# base-v2.net
KiCad netlist of a schematic drawn in EAGLE
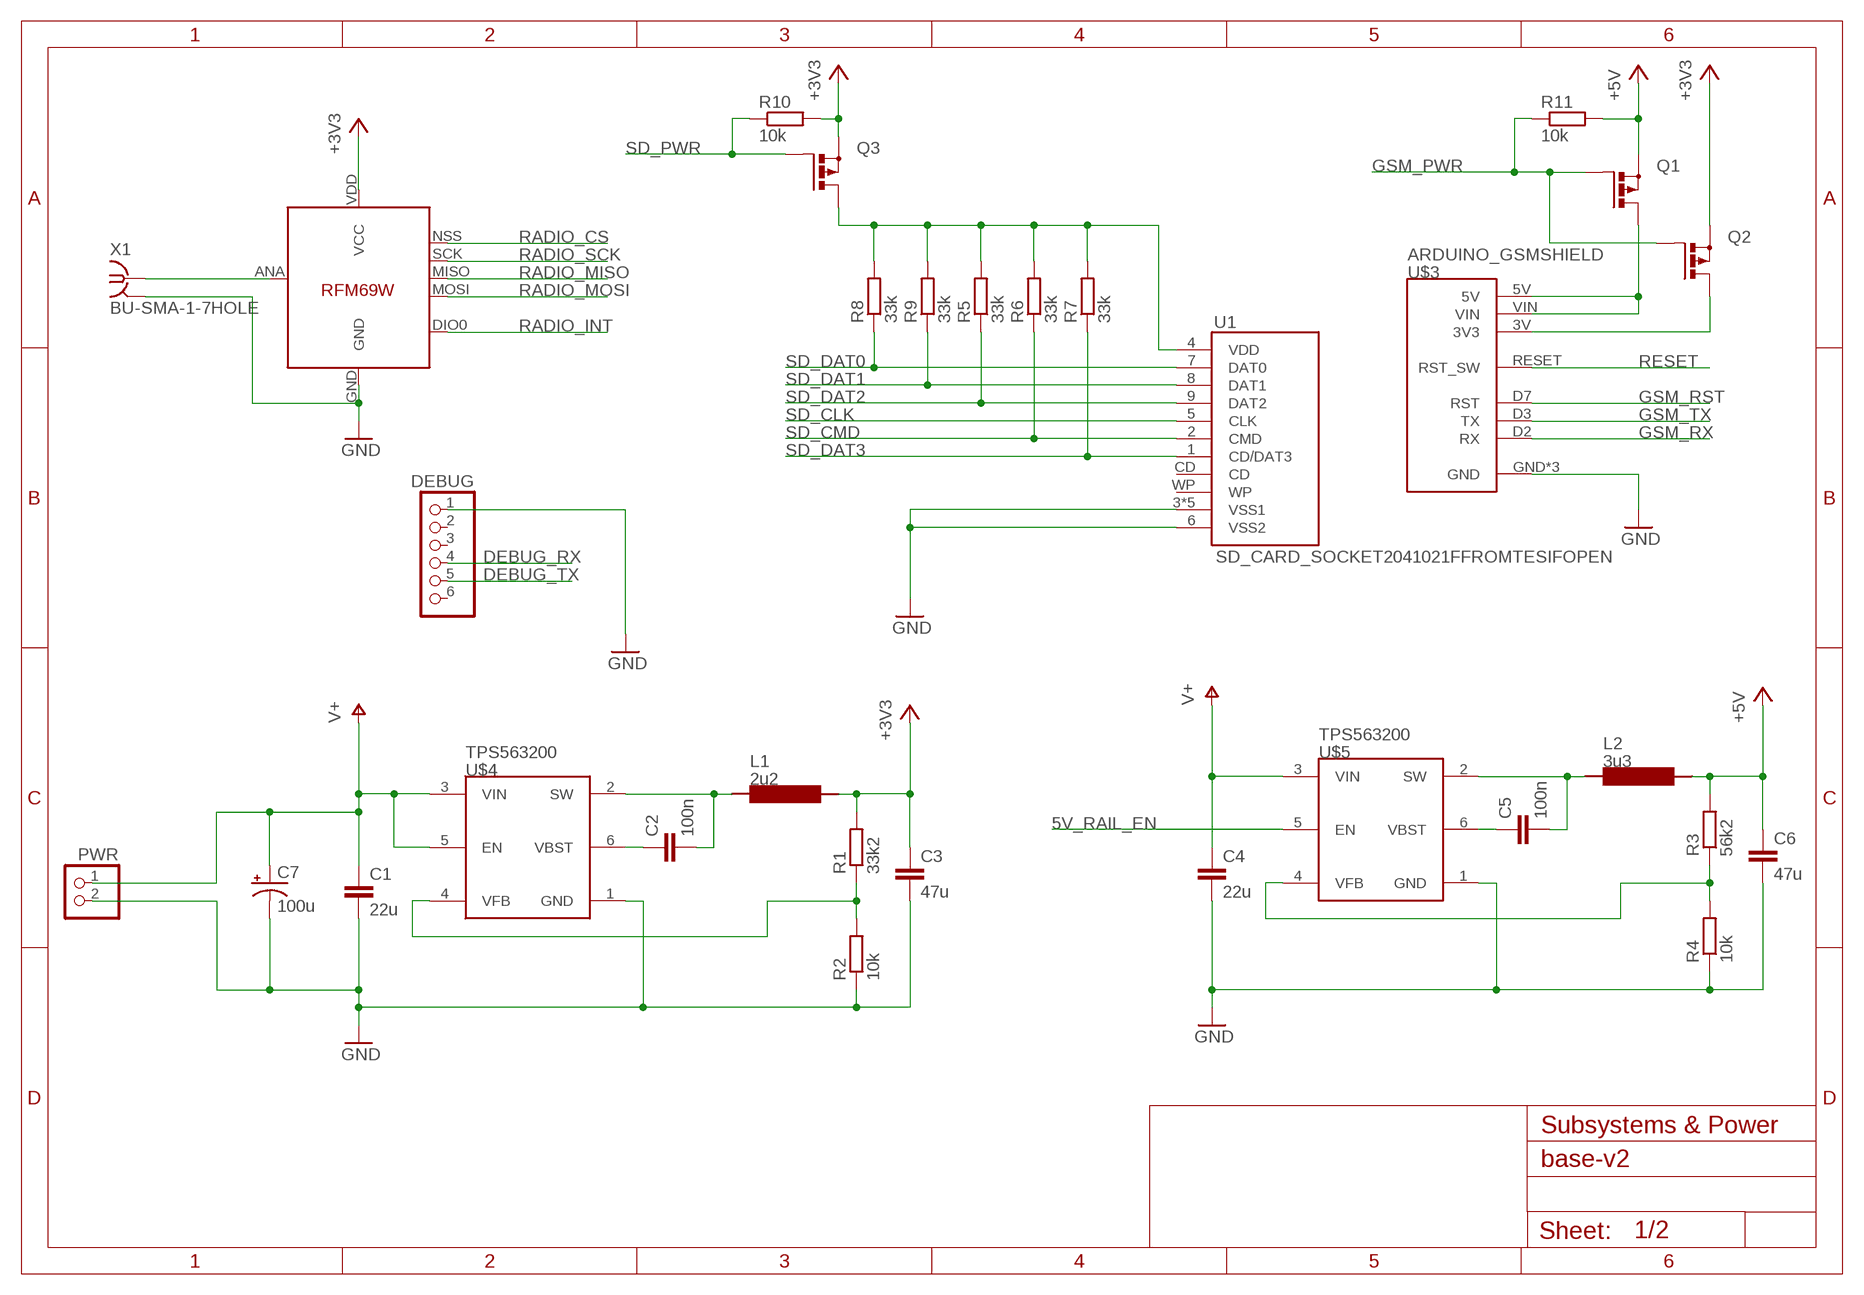
[diagram p0: schematic, sheet 1]
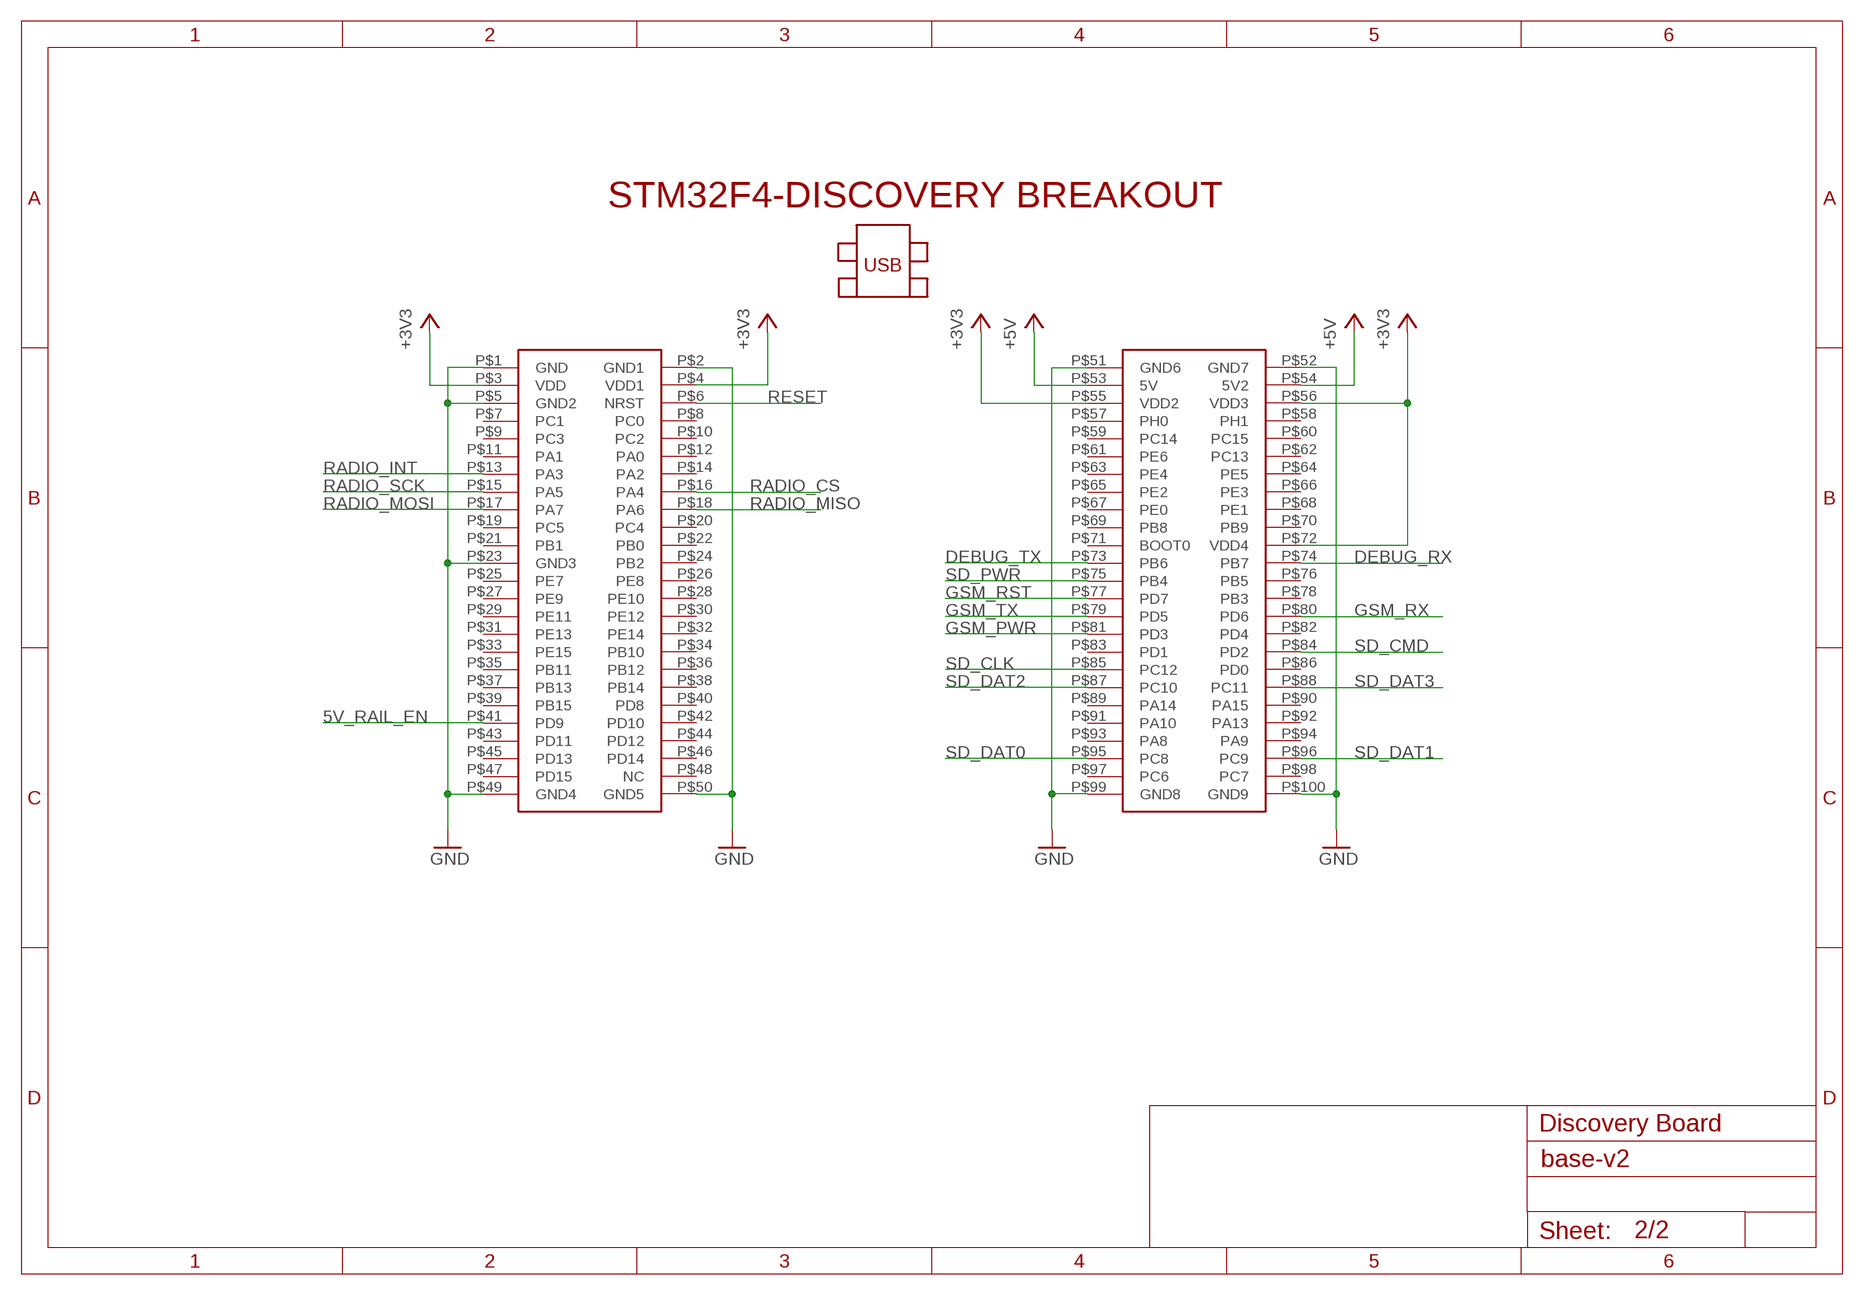
[diagram p1: schematic, sheet 2]

(export (version "E")
  (design (tool "Eeschema 10.0.6"))
  (components
    (comp (ref "C1")
      (value "22u")
      (footprint "eagle-import:1206")
      (libsource (lib "eagle-import") (part "CAP1206"))
    )
    (comp (ref "C2")
      (value "100n")
      (footprint "eagle-import:CAP-PTH-SMALL")
      (libsource (lib "eagle-import") (part "CAPPTH"))
    )
    (comp (ref "C3")
      (value "47u")
      (footprint "eagle-import:1206")
      (libsource (lib "eagle-import") (part "CAP1206"))
    )
    (comp (ref "C4")
      (value "22u")
      (footprint "eagle-import:1206")
      (libsource (lib "eagle-import") (part "CAP1206"))
    )
    (comp (ref "C5")
      (value "100n")
      (footprint "eagle-import:CAP-PTH-SMALL")
      (libsource (lib "eagle-import") (part "CAPPTH"))
    )
    (comp (ref "C6")
      (value "47u")
      (footprint "eagle-import:1206")
      (libsource (lib "eagle-import") (part "CAP1206"))
    )
    (comp (ref "C7")
      (value "100u")
      (footprint "eagle-import:CPOL-RADIAL-10UF-25V")
      (libsource (lib "eagle-import") (part "CAP_POLPTH2"))
    )
    (comp (ref "DEBUG")
      (value "PINHD-1X6")
      (footprint "eagle-import:1X06")
      (libsource (lib "eagle-import") (part "PINHD-1X6"))
    )
    (comp (ref "L1")
      (value "2u2")
      (footprint "eagle-import:SRR7032")
      (libsource (lib "eagle-import") (part "SRR7032"))
    )
    (comp (ref "L2")
      (value "3u3")
      (footprint "eagle-import:SRR7032")
      (libsource (lib "eagle-import") (part "SRR7032"))
    )
    (comp (ref "PWR")
      (value "PINHD-1X2")
      (footprint "eagle-import:1X02")
      (libsource (lib "eagle-import") (part "PINHD-1X2"))
    )
    (comp (ref "Q1")
      (value "PMOSFET_PTO220BH")
      (footprint "eagle-import:TO220BH")
      (libsource (lib "eagle-import") (part "PMOSFET_PTO220BH"))
    )
    (comp (ref "Q2")
      (value "PMOSFET_PTO220BH")
      (footprint "eagle-import:TO220BH")
      (libsource (lib "eagle-import") (part "PMOSFET_PTO220BH"))
    )
    (comp (ref "Q3")
      (value "PMOSFET_PTO220BH")
      (footprint "eagle-import:TO220BH")
      (libsource (lib "eagle-import") (part "PMOSFET_PTO220BH"))
    )
    (comp (ref "R1")
      (value "33k2")
      (footprint "eagle-import:0204_7")
      (libsource (lib "eagle-import") (part "R-EU_0204/7"))
    )
    (comp (ref "R2")
      (value "10k")
      (footprint "eagle-import:0204_7")
      (libsource (lib "eagle-import") (part "R-EU_0204/7"))
    )
    (comp (ref "R3")
      (value "56k2")
      (footprint "eagle-import:0204_7")
      (libsource (lib "eagle-import") (part "R-EU_0204/7"))
    )
    (comp (ref "R4")
      (value "10k")
      (footprint "eagle-import:0204_7")
      (libsource (lib "eagle-import") (part "R-EU_0204/7"))
    )
    (comp (ref "R5")
      (value "33k")
      (footprint "eagle-import:0204_7")
      (libsource (lib "eagle-import") (part "R-EU_0204/7"))
    )
    (comp (ref "R6")
      (value "33k")
      (footprint "eagle-import:0204_7")
      (libsource (lib "eagle-import") (part "R-EU_0204/7"))
    )
    (comp (ref "R7")
      (value "33k")
      (footprint "eagle-import:0204_7")
      (libsource (lib "eagle-import") (part "R-EU_0204/7"))
    )
    (comp (ref "R8")
      (value "33k")
      (footprint "eagle-import:0204_7")
      (libsource (lib "eagle-import") (part "R-EU_0204/7"))
    )
    (comp (ref "R9")
      (value "33k")
      (footprint "eagle-import:0204_7")
      (libsource (lib "eagle-import") (part "R-EU_0204/7"))
    )
    (comp (ref "R10")
      (value "10k")
      (footprint "eagle-import:0204_7")
      (libsource (lib "eagle-import") (part "R-EU_0204/7"))
    )
    (comp (ref "R11")
      (value "10k")
      (footprint "eagle-import:0204_7")
      (libsource (lib "eagle-import") (part "R-EU_0204/7"))
    )
    (comp (ref "U$2")
      (value "RFM69")
      (footprint "eagle-import:RFM69W-MINPADS")
      (libsource (lib "eagle-import") (part "RFM69"))
    )
    (comp (ref "U$3")
      (value "ARDUINO_GSMSHIELD")
      (footprint "eagle-import:ARDUINO-NOHOLE")
      (libsource (lib "eagle-import") (part "ARDUINO_GSMSHIELD"))
    )
    (comp (ref "U$4")
      (value "TPS563200")
      (footprint "eagle-import:DDC0006A")
      (libsource (lib "eagle-import") (part "TPS563200"))
    )
    (comp (ref "U$5")
      (value "TPS563200")
      (footprint "eagle-import:DDC0006A")
      (libsource (lib "eagle-import") (part "TPS563200"))
    )
    (comp (ref "U1")
      (value "SD_CARD_SOCKET2041021FFROMTESIFOPEN")
      (footprint "eagle-import:SDCARD_2041021-3")
      (libsource (lib "eagle-import") (part "SD_CARD_SOCKET2041021FFROMTESIFOPEN"))
    )
    (comp (ref "X1")
      (value "BU-SMA-1-7HOLE")
      (footprint "eagle-import:SMA_1-7HOLES")
      (libsource (lib "eagle-import") (part "BU-SMA-1-7HOLE"))
    )
    (comp (ref "U$1")
      (value "STM32F4-DISCOVERY")
      (footprint "eagle-import:STM32F4-DISCOVERY")
      (libsource (lib "eagle-import") (part "STM32F4-DISCOVERY"))
    )
  )
  (nets
    (net (code "1") (name "+3V3") (class "Default")
      (node (ref "C3") (pin "1") (pinfunction "1_1") (pintype "passive"))
      (node (ref "L1") (pin "2") (pinfunction "2_2") (pintype "passive"))
      (node (ref "Q2") (pin "S") (pinfunction "S_S") (pintype "passive"))
      (node (ref "Q3") (pin "S") (pinfunction "S_S") (pintype "passive"))
      (node (ref "R1") (pin "2") (pinfunction "2_2") (pintype "passive"))
      (node (ref "R10") (pin "2") (pinfunction "2_2") (pintype "passive"))
      (node (ref "U$1") (pin "P$3") (pinfunction "VDD_P$3") (pintype "bidirectional"))
      (node (ref "U$1") (pin "P$4") (pinfunction "VDD1_P$4") (pintype "bidirectional"))
      (node (ref "U$1") (pin "P$55") (pinfunction "VDD2_P$55") (pintype "bidirectional"))
      (node (ref "U$1") (pin "P$56") (pinfunction "VDD3_P$56") (pintype "bidirectional"))
      (node (ref "U$1") (pin "P$72") (pinfunction "VDD4_P$72") (pintype "bidirectional"))
      (node (ref "U$2") (pin "VDD") (pinfunction "VCC_VDD") (pintype "power_in"))
    )
    (net (code "2") (name "+5V") (class "Default")
      (node (ref "C6") (pin "1") (pinfunction "1_1") (pintype "passive"))
      (node (ref "L2") (pin "2") (pinfunction "2_2") (pintype "passive"))
      (node (ref "Q1") (pin "S") (pinfunction "S_S") (pintype "passive"))
      (node (ref "R11") (pin "2") (pinfunction "2_2") (pintype "passive"))
      (node (ref "R3") (pin "2") (pinfunction "2_2") (pintype "passive"))
      (node (ref "U$1") (pin "P$53") (pinfunction "5V_P$53") (pintype "bidirectional"))
      (node (ref "U$1") (pin "P$54") (pinfunction "5V2_P$54") (pintype "bidirectional"))
    )
    (net (code "3") (name "5V_RAIL_EN") (class "Default")
      (node (ref "U$1") (pin "P$41") (pinfunction "PD9_P$41") (pintype "bidirectional"))
      (node (ref "U$5") (pin "5") (pinfunction "EN_5") (pintype "bidirectional"))
    )
    (net (code "4") (name "DEBUG_RX") (class "Default")
      (node (ref "DEBUG") (pin "4") (pinfunction "4_4") (pintype "passive"))
      (node (ref "U$1") (pin "P$74") (pinfunction "PB7_P$74") (pintype "bidirectional"))
    )
    (net (code "5") (name "DEBUG_TX") (class "Default")
      (node (ref "DEBUG") (pin "5") (pinfunction "5_5") (pintype "passive"))
      (node (ref "U$1") (pin "P$73") (pinfunction "PB6_P$73") (pintype "bidirectional"))
    )
    (net (code "6") (name "GND") (class "Default")
      (node (ref "C1") (pin "2") (pinfunction "2_2") (pintype "passive"))
      (node (ref "C3") (pin "2") (pinfunction "2_2") (pintype "passive"))
      (node (ref "C4") (pin "2") (pinfunction "2_2") (pintype "passive"))
      (node (ref "C6") (pin "2") (pinfunction "2_2") (pintype "passive"))
      (node (ref "C7") (pin "2") (pinfunction "-_2") (pintype "passive"))
      (node (ref "DEBUG") (pin "1") (pinfunction "1_1") (pintype "passive"))
      (node (ref "PWR") (pin "2") (pinfunction "2_2") (pintype "passive"))
      (node (ref "R2") (pin "1") (pinfunction "1_1") (pintype "passive"))
      (node (ref "R4") (pin "1") (pinfunction "1_1") (pintype "passive"))
      (node (ref "U$1") (pin "P$1") (pinfunction "GND_P$1") (pintype "bidirectional"))
      (node (ref "U$1") (pin "P$100") (pinfunction "GND9_P$100") (pintype "bidirectional"))
      (node (ref "U$1") (pin "P$2") (pinfunction "GND1_P$2") (pintype "bidirectional"))
      (node (ref "U$1") (pin "P$23") (pinfunction "GND3_P$23") (pintype "bidirectional"))
      (node (ref "U$1") (pin "P$49") (pinfunction "GND4_P$49") (pintype "bidirectional"))
      (node (ref "U$1") (pin "P$5") (pinfunction "GND2_P$5") (pintype "bidirectional"))
      (node (ref "U$1") (pin "P$50") (pinfunction "GND5_P$50") (pintype "bidirectional"))
      (node (ref "U$1") (pin "P$51") (pinfunction "GND6_P$51") (pintype "bidirectional"))
      (node (ref "U$1") (pin "P$52") (pinfunction "GND7_P$52") (pintype "bidirectional"))
      (node (ref "U$1") (pin "P$99") (pinfunction "GND8_P$99") (pintype "bidirectional"))
      (node (ref "U$2") (pin "GND") (pinfunction "GND_GND") (pintype "power_in"))
      (node (ref "U$3") (pin "GND") (pinfunction "GND_GND") (pintype "bidirectional"))
      (node (ref "U$3") (pin "GND1") (pinfunction "GND_GND1") (pintype "bidirectional"))
      (node (ref "U$3") (pin "GND2") (pinfunction "GND_GND2") (pintype "bidirectional"))
      (node (ref "U$4") (pin "1") (pinfunction "GND_1") (pintype "bidirectional"))
      (node (ref "U$5") (pin "1") (pinfunction "GND_1") (pintype "bidirectional"))
      (node (ref "U1") (pin "3") (pinfunction "VSS1_3") (pintype "power_in"))
      (node (ref "U1") (pin "6") (pinfunction "VSS2_6") (pintype "power_in"))
      (node (ref "U1") (pin "SH1") (pinfunction "VSS1_SH1") (pintype "power_in"))
      (node (ref "U1") (pin "SH2") (pinfunction "VSS1_SH2") (pintype "power_in"))
      (node (ref "U1") (pin "SH3") (pinfunction "VSS1_SH3") (pintype "power_in"))
      (node (ref "U1") (pin "SH4") (pinfunction "VSS1_SH4") (pintype "power_in"))
      (node (ref "X1") (pin "2") (pinfunction "2_2") (pintype "passive"))
      (node (ref "X1") (pin "3") (pinfunction "2_3") (pintype "passive"))
      (node (ref "X1") (pin "4") (pinfunction "2_4") (pintype "passive"))
      (node (ref "X1") (pin "5") (pinfunction "2_5") (pintype "passive"))
    )
    (net (code "7") (name "GSM_PWR") (class "Default")
      (node (ref "Q1") (pin "G") (pinfunction "G_G") (pintype "passive"))
      (node (ref "Q2") (pin "G") (pinfunction "G_G") (pintype "passive"))
      (node (ref "R11") (pin "1") (pinfunction "1_1") (pintype "passive"))
      (node (ref "U$1") (pin "P$81") (pinfunction "PD3_P$81") (pintype "bidirectional"))
    )
    (net (code "8") (name "GSM_RST") (class "Default")
      (node (ref "U$1") (pin "P$77") (pinfunction "PD7_P$77") (pintype "bidirectional"))
      (node (ref "U$3") (pin "D7") (pinfunction "RST_D7") (pintype "bidirectional"))
    )
    (net (code "9") (name "GSM_RX") (class "Default")
      (node (ref "U$1") (pin "P$80") (pinfunction "PD6_P$80") (pintype "bidirectional"))
      (node (ref "U$3") (pin "D2") (pinfunction "RX_D2") (pintype "bidirectional"))
    )
    (net (code "10") (name "GSM_TX") (class "Default")
      (node (ref "U$1") (pin "P$79") (pinfunction "PD5_P$79") (pintype "bidirectional"))
      (node (ref "U$3") (pin "D3") (pinfunction "TX_D3") (pintype "bidirectional"))
    )
    (net (code "11") (name "Net-(Q1-PadD)") (class "Default")
      (node (ref "Q1") (pin "D") (pinfunction "D_D") (pintype "passive"))
      (node (ref "U$3") (pin "5V") (pinfunction "5V_5V") (pintype "bidirectional"))
      (node (ref "U$3") (pin "VIN") (pinfunction "VIN_VIN") (pintype "bidirectional"))
    )
    (net (code "12") (name "Net-(U$2-ANT)") (class "Default")
      (node (ref "U$2") (pin "ANA") (pinfunction "ANT_ANA") (pintype "passive"))
      (node (ref "X1") (pin "1") (pinfunction "1_1") (pintype "passive"))
    )
    (net (code "13") (name "Net-(U$3-3V3)") (class "Default")
      (node (ref "Q2") (pin "D") (pinfunction "D_D") (pintype "passive"))
      (node (ref "U$3") (pin "3V") (pinfunction "3V3_3V") (pintype "bidirectional"))
    )
    (net (code "14") (name "Net-(U$4-SW)") (class "Default")
      (node (ref "C2") (pin "2") (pinfunction "2_2") (pintype "passive"))
      (node (ref "L1") (pin "1") (pinfunction "1_1") (pintype "passive"))
      (node (ref "U$4") (pin "2") (pinfunction "SW_2") (pintype "bidirectional"))
    )
    (net (code "15") (name "Net-(U$4-VBST)") (class "Default")
      (node (ref "C2") (pin "1") (pinfunction "1_1") (pintype "passive"))
      (node (ref "U$4") (pin "6") (pinfunction "VBST_6") (pintype "bidirectional"))
    )
    (net (code "16") (name "Net-(U$4-VFB)") (class "Default")
      (node (ref "R1") (pin "1") (pinfunction "1_1") (pintype "passive"))
      (node (ref "R2") (pin "2") (pinfunction "2_2") (pintype "passive"))
      (node (ref "U$4") (pin "4") (pinfunction "VFB_4") (pintype "bidirectional"))
    )
    (net (code "17") (name "Net-(U$5-SW)") (class "Default")
      (node (ref "C5") (pin "2") (pinfunction "2_2") (pintype "passive"))
      (node (ref "L2") (pin "1") (pinfunction "1_1") (pintype "passive"))
      (node (ref "U$5") (pin "2") (pinfunction "SW_2") (pintype "bidirectional"))
    )
    (net (code "18") (name "Net-(U$5-VBST)") (class "Default")
      (node (ref "C5") (pin "1") (pinfunction "1_1") (pintype "passive"))
      (node (ref "U$5") (pin "6") (pinfunction "VBST_6") (pintype "bidirectional"))
    )
    (net (code "19") (name "Net-(U$5-VFB)") (class "Default")
      (node (ref "R3") (pin "1") (pinfunction "1_1") (pintype "passive"))
      (node (ref "R4") (pin "2") (pinfunction "2_2") (pintype "passive"))
      (node (ref "U$5") (pin "4") (pinfunction "VFB_4") (pintype "bidirectional"))
    )
    (net (code "20") (name "Net-(U1-VDD)") (class "Default")
      (node (ref "Q3") (pin "D") (pinfunction "D_D") (pintype "passive"))
      (node (ref "R5") (pin "2") (pinfunction "2_2") (pintype "passive"))
      (node (ref "R6") (pin "2") (pinfunction "2_2") (pintype "passive"))
      (node (ref "R7") (pin "2") (pinfunction "2_2") (pintype "passive"))
      (node (ref "R8") (pin "2") (pinfunction "2_2") (pintype "passive"))
      (node (ref "R9") (pin "2") (pinfunction "2_2") (pintype "passive"))
      (node (ref "U1") (pin "4") (pinfunction "VDD_4") (pintype "power_in"))
    )
    (net (code "21") (name "RADIO_CS") (class "Default")
      (node (ref "U$1") (pin "P$16") (pinfunction "PA4_P$16") (pintype "bidirectional"))
      (node (ref "U$2") (pin "NSS") (pinfunction "SEL_NSS") (pintype "input"))
    )
    (net (code "22") (name "RADIO_INT") (class "Default")
      (node (ref "U$1") (pin "P$13") (pinfunction "PA3_P$13") (pintype "bidirectional"))
      (node (ref "U$2") (pin "DIO0") (pinfunction "DIO0_DIO0") (pintype "open_collector"))
    )
    (net (code "23") (name "RADIO_MISO") (class "Default")
      (node (ref "U$1") (pin "P$18") (pinfunction "PA6_P$18") (pintype "bidirectional"))
      (node (ref "U$2") (pin "MISO") (pinfunction "MISO_MISO") (pintype "input"))
    )
    (net (code "24") (name "RADIO_MOSI") (class "Default")
      (node (ref "U$1") (pin "P$17") (pinfunction "PA7_P$17") (pintype "bidirectional"))
      (node (ref "U$2") (pin "MOSI") (pinfunction "MOSI_MOSI") (pintype "output"))
    )
    (net (code "25") (name "RADIO_SCK") (class "Default")
      (node (ref "U$1") (pin "P$15") (pinfunction "PA5_P$15") (pintype "bidirectional"))
      (node (ref "U$2") (pin "SCK") (pinfunction "SCK_SCK") (pintype "input"))
    )
    (net (code "26") (name "RESET") (class "Default")
      (node (ref "U$1") (pin "P$6") (pinfunction "NRST_P$6") (pintype "bidirectional"))
      (node (ref "U$3") (pin "RESET") (pinfunction "RST_SW_RESET") (pintype "bidirectional"))
    )
    (net (code "27") (name "SD_CLK") (class "Default")
      (node (ref "U$1") (pin "P$85") (pinfunction "PC12_P$85") (pintype "bidirectional"))
      (node (ref "U1") (pin "5") (pinfunction "CLK_5") (pintype "bidirectional"))
    )
    (net (code "28") (name "SD_CMD") (class "Default")
      (node (ref "R6") (pin "1") (pinfunction "1_1") (pintype "passive"))
      (node (ref "U$1") (pin "P$84") (pinfunction "PD2_P$84") (pintype "bidirectional"))
      (node (ref "U1") (pin "2") (pinfunction "CMD_2") (pintype "bidirectional"))
    )
    (net (code "29") (name "SD_DAT0") (class "Default")
      (node (ref "R8") (pin "1") (pinfunction "1_1") (pintype "passive"))
      (node (ref "U$1") (pin "P$95") (pinfunction "PC8_P$95") (pintype "bidirectional"))
      (node (ref "U1") (pin "7") (pinfunction "DAT0_7") (pintype "bidirectional"))
    )
    (net (code "30") (name "SD_DAT1") (class "Default")
      (node (ref "R9") (pin "1") (pinfunction "1_1") (pintype "passive"))
      (node (ref "U$1") (pin "P$96") (pinfunction "PC9_P$96") (pintype "bidirectional"))
      (node (ref "U1") (pin "8") (pinfunction "DAT1_8") (pintype "bidirectional"))
    )
    (net (code "31") (name "SD_DAT2") (class "Default")
      (node (ref "R5") (pin "1") (pinfunction "1_1") (pintype "passive"))
      (node (ref "U$1") (pin "P$87") (pinfunction "PC10_P$87") (pintype "bidirectional"))
      (node (ref "U1") (pin "9") (pinfunction "DAT2_9") (pintype "bidirectional"))
    )
    (net (code "32") (name "SD_DAT3") (class "Default")
      (node (ref "R7") (pin "1") (pinfunction "1_1") (pintype "passive"))
      (node (ref "U$1") (pin "P$88") (pinfunction "PC11_P$88") (pintype "bidirectional"))
      (node (ref "U1") (pin "1") (pinfunction "CD/DAT3_1") (pintype "bidirectional"))
    )
    (net (code "33") (name "SD_PWR") (class "Default")
      (node (ref "Q3") (pin "G") (pinfunction "G_G") (pintype "passive"))
      (node (ref "R10") (pin "1") (pinfunction "1_1") (pintype "passive"))
      (node (ref "U$1") (pin "P$75") (pinfunction "PB4_P$75") (pintype "bidirectional"))
    )
    (net (code "34") (name "V+") (class "Default")
      (node (ref "C1") (pin "1") (pinfunction "1_1") (pintype "passive"))
      (node (ref "C4") (pin "1") (pinfunction "1_1") (pintype "passive"))
      (node (ref "C7") (pin "1") (pinfunction "+_1") (pintype "passive"))
      (node (ref "PWR") (pin "1") (pinfunction "1_1") (pintype "passive"))
      (node (ref "U$4") (pin "3") (pinfunction "VIN_3") (pintype "bidirectional"))
      (node (ref "U$4") (pin "5") (pinfunction "EN_5") (pintype "bidirectional"))
      (node (ref "U$5") (pin "3") (pinfunction "VIN_3") (pintype "bidirectional"))
    )
    (net (code "35") (name "unconnected-(DEBUG-Pad2)") (class "Default")
      (node (ref "DEBUG") (pin "2") (pinfunction "2_2") (pintype "passive"))
    )
    (net (code "36") (name "unconnected-(DEBUG-Pad3)") (class "Default")
      (node (ref "DEBUG") (pin "3") (pinfunction "3_3") (pintype "passive"))
    )
    (net (code "37") (name "unconnected-(DEBUG-Pad6)") (class "Default")
      (node (ref "DEBUG") (pin "6") (pinfunction "6_6") (pintype "passive"))
    )
    (net (code "38") (name "unconnected-(U$1-BOOT0-PadP$71)") (class "Default")
      (node (ref "U$1") (pin "P$71") (pinfunction "BOOT0_P$71") (pintype "bidirectional"))
    )
    (net (code "39") (name "unconnected-(U$1-NC-PadP$48)") (class "Default")
      (node (ref "U$1") (pin "P$48") (pinfunction "NC_P$48") (pintype "bidirectional"))
    )
    (net (code "40") (name "unconnected-(U$1-PA0-PadP$12)") (class "Default")
      (node (ref "U$1") (pin "P$12") (pinfunction "PA0_P$12") (pintype "bidirectional"))
    )
    (net (code "41") (name "unconnected-(U$1-PA1-PadP$11)") (class "Default")
      (node (ref "U$1") (pin "P$11") (pinfunction "PA1_P$11") (pintype "bidirectional"))
    )
    (net (code "42") (name "unconnected-(U$1-PA2-PadP$14)") (class "Default")
      (node (ref "U$1") (pin "P$14") (pinfunction "PA2_P$14") (pintype "bidirectional"))
    )
    (net (code "43") (name "unconnected-(U$1-PA8-PadP$93)") (class "Default")
      (node (ref "U$1") (pin "P$93") (pinfunction "PA8_P$93") (pintype "bidirectional"))
    )
    (net (code "44") (name "unconnected-(U$1-PA9-PadP$94)") (class "Default")
      (node (ref "U$1") (pin "P$94") (pinfunction "PA9_P$94") (pintype "bidirectional"))
    )
    (net (code "45") (name "unconnected-(U$1-PA10-PadP$91)") (class "Default")
      (node (ref "U$1") (pin "P$91") (pinfunction "PA10_P$91") (pintype "bidirectional"))
    )
    (net (code "46") (name "unconnected-(U$1-PA13-PadP$92)") (class "Default")
      (node (ref "U$1") (pin "P$92") (pinfunction "PA13_P$92") (pintype "bidirectional"))
    )
    (net (code "47") (name "unconnected-(U$1-PA14-PadP$89)") (class "Default")
      (node (ref "U$1") (pin "P$89") (pinfunction "PA14_P$89") (pintype "bidirectional"))
    )
    (net (code "48") (name "unconnected-(U$1-PA15-PadP$90)") (class "Default")
      (node (ref "U$1") (pin "P$90") (pinfunction "PA15_P$90") (pintype "bidirectional"))
    )
    (net (code "49") (name "unconnected-(U$1-PB0-PadP$22)") (class "Default")
      (node (ref "U$1") (pin "P$22") (pinfunction "PB0_P$22") (pintype "bidirectional"))
    )
    (net (code "50") (name "unconnected-(U$1-PB1-PadP$21)") (class "Default")
      (node (ref "U$1") (pin "P$21") (pinfunction "PB1_P$21") (pintype "bidirectional"))
    )
    (net (code "51") (name "unconnected-(U$1-PB2-PadP$24)") (class "Default")
      (node (ref "U$1") (pin "P$24") (pinfunction "PB2_P$24") (pintype "bidirectional"))
    )
    (net (code "52") (name "unconnected-(U$1-PB3-PadP$78)") (class "Default")
      (node (ref "U$1") (pin "P$78") (pinfunction "PB3_P$78") (pintype "bidirectional"))
    )
    (net (code "53") (name "unconnected-(U$1-PB5-PadP$76)") (class "Default")
      (node (ref "U$1") (pin "P$76") (pinfunction "PB5_P$76") (pintype "bidirectional"))
    )
    (net (code "54") (name "unconnected-(U$1-PB8-PadP$69)") (class "Default")
      (node (ref "U$1") (pin "P$69") (pinfunction "PB8_P$69") (pintype "bidirectional"))
    )
    (net (code "55") (name "unconnected-(U$1-PB9-PadP$70)") (class "Default")
      (node (ref "U$1") (pin "P$70") (pinfunction "PB9_P$70") (pintype "bidirectional"))
    )
    (net (code "56") (name "unconnected-(U$1-PB10-PadP$34)") (class "Default")
      (node (ref "U$1") (pin "P$34") (pinfunction "PB10_P$34") (pintype "bidirectional"))
    )
    (net (code "57") (name "unconnected-(U$1-PB11-PadP$35)") (class "Default")
      (node (ref "U$1") (pin "P$35") (pinfunction "PB11_P$35") (pintype "bidirectional"))
    )
    (net (code "58") (name "unconnected-(U$1-PB12-PadP$36)") (class "Default")
      (node (ref "U$1") (pin "P$36") (pinfunction "PB12_P$36") (pintype "bidirectional"))
    )
    (net (code "59") (name "unconnected-(U$1-PB13-PadP$37)") (class "Default")
      (node (ref "U$1") (pin "P$37") (pinfunction "PB13_P$37") (pintype "bidirectional"))
    )
    (net (code "60") (name "unconnected-(U$1-PB14-PadP$38)") (class "Default")
      (node (ref "U$1") (pin "P$38") (pinfunction "PB14_P$38") (pintype "bidirectional"))
    )
    (net (code "61") (name "unconnected-(U$1-PB15-PadP$39)") (class "Default")
      (node (ref "U$1") (pin "P$39") (pinfunction "PB15_P$39") (pintype "bidirectional"))
    )
    (net (code "62") (name "unconnected-(U$1-PC0-PadP$8)") (class "Default")
      (node (ref "U$1") (pin "P$8") (pinfunction "PC0_P$8") (pintype "bidirectional"))
    )
    (net (code "63") (name "unconnected-(U$1-PC1-PadP$7)") (class "Default")
      (node (ref "U$1") (pin "P$7") (pinfunction "PC1_P$7") (pintype "bidirectional"))
    )
    (net (code "64") (name "unconnected-(U$1-PC2-PadP$10)") (class "Default")
      (node (ref "U$1") (pin "P$10") (pinfunction "PC2_P$10") (pintype "bidirectional"))
    )
    (net (code "65") (name "unconnected-(U$1-PC3-PadP$9)") (class "Default")
      (node (ref "U$1") (pin "P$9") (pinfunction "PC3_P$9") (pintype "bidirectional"))
    )
    (net (code "66") (name "unconnected-(U$1-PC4-PadP$20)") (class "Default")
      (node (ref "U$1") (pin "P$20") (pinfunction "PC4_P$20") (pintype "bidirectional"))
    )
    (net (code "67") (name "unconnected-(U$1-PC5-PadP$19)") (class "Default")
      (node (ref "U$1") (pin "P$19") (pinfunction "PC5_P$19") (pintype "bidirectional"))
    )
    (net (code "68") (name "unconnected-(U$1-PC6-PadP$97)") (class "Default")
      (node (ref "U$1") (pin "P$97") (pinfunction "PC6_P$97") (pintype "bidirectional"))
    )
    (net (code "69") (name "unconnected-(U$1-PC7-PadP$98)") (class "Default")
      (node (ref "U$1") (pin "P$98") (pinfunction "PC7_P$98") (pintype "bidirectional"))
    )
    (net (code "70") (name "unconnected-(U$1-PC13-PadP$62)") (class "Default")
      (node (ref "U$1") (pin "P$62") (pinfunction "PC13_P$62") (pintype "bidirectional"))
    )
    (net (code "71") (name "unconnected-(U$1-PC14-PadP$59)") (class "Default")
      (node (ref "U$1") (pin "P$59") (pinfunction "PC14_P$59") (pintype "bidirectional"))
    )
    (net (code "72") (name "unconnected-(U$1-PC15-PadP$60)") (class "Default")
      (node (ref "U$1") (pin "P$60") (pinfunction "PC15_P$60") (pintype "bidirectional"))
    )
    (net (code "73") (name "unconnected-(U$1-PD0-PadP$86)") (class "Default")
      (node (ref "U$1") (pin "P$86") (pinfunction "PD0_P$86") (pintype "bidirectional"))
    )
    (net (code "74") (name "unconnected-(U$1-PD1-PadP$83)") (class "Default")
      (node (ref "U$1") (pin "P$83") (pinfunction "PD1_P$83") (pintype "bidirectional"))
    )
    (net (code "75") (name "unconnected-(U$1-PD4-PadP$82)") (class "Default")
      (node (ref "U$1") (pin "P$82") (pinfunction "PD4_P$82") (pintype "bidirectional"))
    )
    (net (code "76") (name "unconnected-(U$1-PD8-PadP$40)") (class "Default")
      (node (ref "U$1") (pin "P$40") (pinfunction "PD8_P$40") (pintype "bidirectional"))
    )
    (net (code "77") (name "unconnected-(U$1-PD10-PadP$42)") (class "Default")
      (node (ref "U$1") (pin "P$42") (pinfunction "PD10_P$42") (pintype "bidirectional"))
    )
    (net (code "78") (name "unconnected-(U$1-PD11-PadP$43)") (class "Default")
      (node (ref "U$1") (pin "P$43") (pinfunction "PD11_P$43") (pintype "bidirectional"))
    )
    (net (code "79") (name "unconnected-(U$1-PD12-PadP$44)") (class "Default")
      (node (ref "U$1") (pin "P$44") (pinfunction "PD12_P$44") (pintype "bidirectional"))
    )
    (net (code "80") (name "unconnected-(U$1-PD13-PadP$45)") (class "Default")
      (node (ref "U$1") (pin "P$45") (pinfunction "PD13_P$45") (pintype "bidirectional"))
    )
    (net (code "81") (name "unconnected-(U$1-PD14-PadP$46)") (class "Default")
      (node (ref "U$1") (pin "P$46") (pinfunction "PD14_P$46") (pintype "bidirectional"))
    )
    (net (code "82") (name "unconnected-(U$1-PD15-PadP$47)") (class "Default")
      (node (ref "U$1") (pin "P$47") (pinfunction "PD15_P$47") (pintype "bidirectional"))
    )
    (net (code "83") (name "unconnected-(U$1-PE0-PadP$67)") (class "Default")
      (node (ref "U$1") (pin "P$67") (pinfunction "PE0_P$67") (pintype "bidirectional"))
    )
    (net (code "84") (name "unconnected-(U$1-PE1-PadP$68)") (class "Default")
      (node (ref "U$1") (pin "P$68") (pinfunction "PE1_P$68") (pintype "bidirectional"))
    )
    (net (code "85") (name "unconnected-(U$1-PE2-PadP$65)") (class "Default")
      (node (ref "U$1") (pin "P$65") (pinfunction "PE2_P$65") (pintype "bidirectional"))
    )
    (net (code "86") (name "unconnected-(U$1-PE3-PadP$66)") (class "Default")
      (node (ref "U$1") (pin "P$66") (pinfunction "PE3_P$66") (pintype "bidirectional"))
    )
    (net (code "87") (name "unconnected-(U$1-PE4-PadP$63)") (class "Default")
      (node (ref "U$1") (pin "P$63") (pinfunction "PE4_P$63") (pintype "bidirectional"))
    )
    (net (code "88") (name "unconnected-(U$1-PE5-PadP$64)") (class "Default")
      (node (ref "U$1") (pin "P$64") (pinfunction "PE5_P$64") (pintype "bidirectional"))
    )
    (net (code "89") (name "unconnected-(U$1-PE6-PadP$61)") (class "Default")
      (node (ref "U$1") (pin "P$61") (pinfunction "PE6_P$61") (pintype "bidirectional"))
    )
    (net (code "90") (name "unconnected-(U$1-PE7-PadP$25)") (class "Default")
      (node (ref "U$1") (pin "P$25") (pinfunction "PE7_P$25") (pintype "bidirectional"))
    )
    (net (code "91") (name "unconnected-(U$1-PE8-PadP$26)") (class "Default")
      (node (ref "U$1") (pin "P$26") (pinfunction "PE8_P$26") (pintype "bidirectional"))
    )
    (net (code "92") (name "unconnected-(U$1-PE9-PadP$27)") (class "Default")
      (node (ref "U$1") (pin "P$27") (pinfunction "PE9_P$27") (pintype "bidirectional"))
    )
    (net (code "93") (name "unconnected-(U$1-PE10-PadP$28)") (class "Default")
      (node (ref "U$1") (pin "P$28") (pinfunction "PE10_P$28") (pintype "bidirectional"))
    )
    (net (code "94") (name "unconnected-(U$1-PE11-PadP$29)") (class "Default")
      (node (ref "U$1") (pin "P$29") (pinfunction "PE11_P$29") (pintype "bidirectional"))
    )
    (net (code "95") (name "unconnected-(U$1-PE12-PadP$30)") (class "Default")
      (node (ref "U$1") (pin "P$30") (pinfunction "PE12_P$30") (pintype "bidirectional"))
    )
    (net (code "96") (name "unconnected-(U$1-PE13-PadP$31)") (class "Default")
      (node (ref "U$1") (pin "P$31") (pinfunction "PE13_P$31") (pintype "bidirectional"))
    )
    (net (code "97") (name "unconnected-(U$1-PE14-PadP$32)") (class "Default")
      (node (ref "U$1") (pin "P$32") (pinfunction "PE14_P$32") (pintype "bidirectional"))
    )
    (net (code "98") (name "unconnected-(U$1-PE15-PadP$33)") (class "Default")
      (node (ref "U$1") (pin "P$33") (pinfunction "PE15_P$33") (pintype "bidirectional"))
    )
    (net (code "99") (name "unconnected-(U$1-PH0-PadP$57)") (class "Default")
      (node (ref "U$1") (pin "P$57") (pinfunction "PH0_P$57") (pintype "bidirectional"))
    )
    (net (code "100") (name "unconnected-(U$1-PH1-PadP$58)") (class "Default")
      (node (ref "U$1") (pin "P$58") (pinfunction "PH1_P$58") (pintype "bidirectional"))
    )
    (net (code "101") (name "unconnected-(U1-PadCD)") (class "Default")
      (node (ref "U1") (pin "CD") (pinfunction "CD_CD") (pintype "bidirectional"))
    )
    (net (code "102") (name "unconnected-(U1-PadWP)") (class "Default")
      (node (ref "U1") (pin "WP") (pinfunction "WP_WP") (pintype "bidirectional"))
    )
  )
)
